# CONNECTORS.net
KiCad netlist of a schematic drawn in Altium Designer
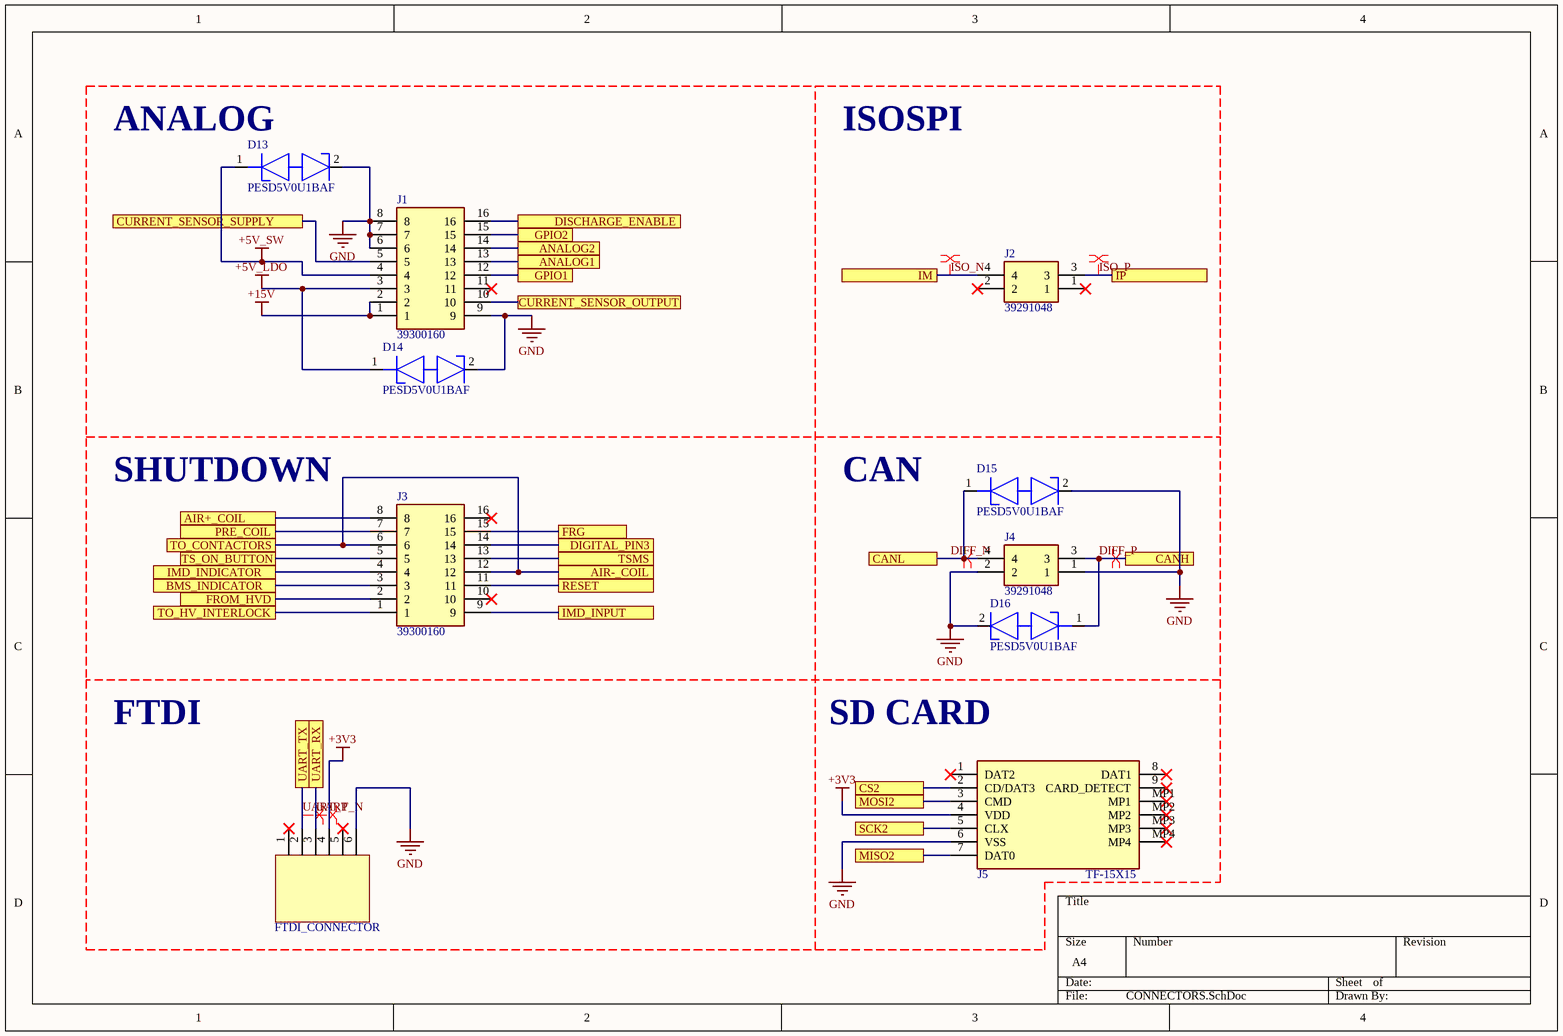
[diagram p0: CONNECTORS.SchDoc]

(export (version "E")
  (design (tool "Eeschema 10.0.6"))
  (components
    (comp (ref "*1")
      (value "FTDI_connector")
      (footprint "ARDUINO_MEGA_NO_SILK")
      (libsource (lib "Schlib1") (part "FTDI_connector"))
    )
    (comp (ref "D13")
      (value "PESD5V0U1BAF")
      (footprint "Regular_used_components_3D_Symbol:SOD2512X110N")
      (description "Diode ESD (Bi-directional)")
      (fields (field (name "MOUSER PART NUMBER") "771-PESD5V0U1BAF"))
      (libsource (lib "Regular_used_components_2D_Symbol") (part "PESD5V0U1BAF"))
    )
    (comp (ref "D14")
      (value "PESD5V0U1BAF")
      (footprint "Regular_used_components_3D_Symbol:SOD2512X110N")
      (description "Diode ESD (Bi-directional)")
      (fields (field (name "MOUSER PART NUMBER") "771-PESD5V0U1BAF"))
      (libsource (lib "Regular_used_components_2D_Symbol") (part "PESD5V0U1BAF"))
    )
    (comp (ref "D15")
      (value "PESD5V0U1BAF")
      (footprint "Regular_used_components_3D_Symbol:SOD2512X110N")
      (description "Diode ESD (Bi-directional)")
      (fields (field (name "MOUSER PART NUMBER") "771-PESD5V0U1BAF"))
      (libsource (lib "Regular_used_components_2D_Symbol") (part "PESD5V0U1BAF"))
    )
    (comp (ref "D16")
      (value "PESD5V0U1BAF")
      (footprint "Regular_used_components_3D_Symbol:SOD2512X110N")
      (description "Diode ESD (Bi-directional)")
      (fields (field (name "MOUSER PART NUMBER") "771-PESD5V0U1BAF"))
      (libsource (lib "Regular_used_components_2D_Symbol") (part "PESD5V0U1BAF"))
    )
    (comp (ref "J1")
      (value "39300160")
      (footprint "Regular_used_components_3D_Symbol:39300160")
      (description "Connector")
      (libsource (lib "*") (part "39300160"))
    )
    (comp (ref "J2")
      (value "39291048")
      (footprint "SamacSys:3929104Y")
      (description "Connector")
      (libsource (lib "*") (part "39291048"))
    )
    (comp (ref "J3")
      (value "39300160")
      (footprint "Regular_used_components_3D_Symbol:39300160")
      (description "Connector")
      (libsource (lib "*") (part "39300160"))
    )
    (comp (ref "J4")
      (value "39291048")
      (footprint "SamacSys:3929104Y")
      (description "Connector")
      (libsource (lib "*") (part "39291048"))
    )
    (comp (ref "J5")
      (value "TF-15X15")
      (footprint "Regular_used_components_3D_Symbol:TF15X15")
      (description "Connector")
      (libsource (lib "*") (part "TF-15X15"))
    )
  )
  (nets
    (net (code "1") (name "+3V3") (class "Default")
      (node (ref "*1") (pin "4") (pinfunction "4_4") (pintype "passive"))
      (node (ref "J5") (pin "4") (pinfunction "VDD_4") (pintype "passive"))
    )
    (net (code "2") (name "+5V_LDO") (class "Default")
      (node (ref "D14") (pin "1") (pinfunction "K1_1") (pintype "passive"))
      (node (ref "J1") (pin "3") (pinfunction "3_3") (pintype "passive"))
    )
    (net (code "3") (name "+5V_SW") (class "Default")
      (node (ref "D13") (pin "1") (pinfunction "K1_1") (pintype "passive"))
      (node (ref "J1") (pin "4") (pinfunction "4_4") (pintype "passive"))
    )
    (net (code "4") (name "+15V") (class "Default")
      (node (ref "J1") (pin "1") (pinfunction "1_1") (pintype "passive"))
      (node (ref "J1") (pin "2") (pinfunction "2_2") (pintype "passive"))
    )
    (net (code "5") (name "/AIR+_COIL") (class "Default")
      (node (ref "J3") (pin "8") (pinfunction "8_8") (pintype "passive"))
    )
    (net (code "6") (name "/AIR-_COIL") (class "Default")
      (node (ref "J3") (pin "12") (pinfunction "12_12") (pintype "passive"))
      (node (ref "J3") (pin "6") (pinfunction "6_6") (pintype "passive"))
    )
    (net (code "7") (name "/ANALOG1") (class "Default")
      (node (ref "J1") (pin "13") (pinfunction "13_13") (pintype "passive"))
    )
    (net (code "8") (name "/ANALOG2") (class "Default")
      (node (ref "J1") (pin "14") (pinfunction "14_14") (pintype "passive"))
    )
    (net (code "9") (name "/BMS_INDICATOR") (class "Default")
      (node (ref "J3") (pin "3") (pinfunction "3_3") (pintype "passive"))
    )
    (net (code "10") (name "/CS2") (class "Default")
      (node (ref "J5") (pin "2") (pinfunction "CD/DAT3_2") (pintype "passive"))
    )
    (net (code "11") (name "/CURRENT_SENSOR_OUTPUT") (class "Default")
      (node (ref "J1") (pin "10") (pinfunction "10_10") (pintype "passive"))
    )
    (net (code "12") (name "/CURRENT_SENSOR_SUPPLY") (class "Default")
      (node (ref "J1") (pin "5") (pinfunction "5_5") (pintype "passive"))
    )
    (net (code "13") (name "/DIFF_N") (class "Default")
      (node (ref "D15") (pin "1") (pinfunction "K1_1") (pintype "passive"))
      (node (ref "J4") (pin "4") (pinfunction "4_4") (pintype "passive"))
    )
    (net (code "14") (name "/DIFF_P") (class "Default")
      (node (ref "D16") (pin "1") (pinfunction "K1_1") (pintype "passive"))
      (node (ref "J4") (pin "3") (pinfunction "3_3") (pintype "passive"))
    )
    (net (code "15") (name "/DIGITAL_PIN3") (class "Default")
      (node (ref "J3") (pin "14") (pinfunction "14_14") (pintype "passive"))
    )
    (net (code "16") (name "/DISCHARGE_ENABLE") (class "Default")
      (node (ref "J1") (pin "16") (pinfunction "16_16") (pintype "passive"))
    )
    (net (code "17") (name "/FRG") (class "Default")
      (node (ref "J3") (pin "15") (pinfunction "15_15") (pintype "passive"))
    )
    (net (code "18") (name "/FROM_HVD") (class "Default")
      (node (ref "J3") (pin "2") (pinfunction "2_2") (pintype "passive"))
    )
    (net (code "19") (name "/GPIO1") (class "Default")
      (node (ref "J1") (pin "12") (pinfunction "12_12") (pintype "passive"))
    )
    (net (code "20") (name "/GPIO2") (class "Default")
      (node (ref "J1") (pin "15") (pinfunction "15_15") (pintype "passive"))
    )
    (net (code "21") (name "/IMD_INDICATOR") (class "Default")
      (node (ref "J3") (pin "4") (pinfunction "4_4") (pintype "passive"))
    )
    (net (code "22") (name "/IMD_INPUT") (class "Default")
      (node (ref "J3") (pin "9") (pinfunction "9_9") (pintype "passive"))
    )
    (net (code "23") (name "/ISO_N") (class "Default")
      (node (ref "J2") (pin "4") (pinfunction "4_4") (pintype "passive"))
    )
    (net (code "24") (name "/ISO_P") (class "Default")
      (node (ref "J2") (pin "3") (pinfunction "3_3") (pintype "passive"))
    )
    (net (code "25") (name "/MISO2") (class "Default")
      (node (ref "J5") (pin "7") (pinfunction "DAT0_7") (pintype "passive"))
    )
    (net (code "26") (name "/MOSI2") (class "Default")
      (node (ref "J5") (pin "3") (pinfunction "CMD_3") (pintype "passive"))
    )
    (net (code "27") (name "/PRE_COIL") (class "Default")
      (node (ref "J3") (pin "7") (pinfunction "7_7") (pintype "passive"))
    )
    (net (code "28") (name "/RESET") (class "Default")
      (node (ref "J3") (pin "11") (pinfunction "11_11") (pintype "passive"))
    )
    (net (code "29") (name "/SCK2") (class "Default")
      (node (ref "J5") (pin "5") (pinfunction "CLX_5") (pintype "passive"))
    )
    (net (code "30") (name "/TO_HV_INTERLOCK") (class "Default")
      (node (ref "J3") (pin "1") (pinfunction "1_1") (pintype "passive"))
    )
    (net (code "31") (name "/TSMS") (class "Default")
      (node (ref "J3") (pin "13") (pinfunction "13_13") (pintype "passive"))
    )
    (net (code "32") (name "/TS_ON_BUTTON") (class "Default")
      (node (ref "J3") (pin "5") (pinfunction "5_5") (pintype "passive"))
    )
    (net (code "33") (name "/UART_N") (class "Default")
      (node (ref "*1") (pin "3") (pinfunction "4_3") (pintype "passive"))
    )
    (net (code "34") (name "/UART_P") (class "Default")
      (node (ref "*1") (pin "2") (pinfunction "2_2") (pintype "passive"))
    )
    (net (code "35") (name "GND") (class "Default")
      (node (ref "*1") (pin "6") (pinfunction "6_6") (pintype "passive"))
      (node (ref "D13") (pin "2") (pinfunction "K2_2") (pintype "passive"))
      (node (ref "D14") (pin "2") (pinfunction "K2_2") (pintype "passive"))
      (node (ref "D15") (pin "2") (pinfunction "K2_2") (pintype "passive"))
      (node (ref "D16") (pin "2") (pinfunction "K2_2") (pintype "passive"))
      (node (ref "J1") (pin "6") (pinfunction "6_6") (pintype "passive"))
      (node (ref "J1") (pin "7") (pinfunction "7_7") (pintype "passive"))
      (node (ref "J1") (pin "8") (pinfunction "8_8") (pintype "passive"))
      (node (ref "J1") (pin "9") (pinfunction "9_9") (pintype "passive"))
      (node (ref "J4") (pin "1") (pinfunction "1_1") (pintype "passive"))
      (node (ref "J4") (pin "2") (pinfunction "2_2") (pintype "passive"))
      (node (ref "J5") (pin "6") (pinfunction "VSS_6") (pintype "passive"))
    )
    (net (code "36") (name "unconnected-(*1-2-Pad5)") (class "Default")
      (node (ref "*1") (pin "5") (pinfunction "2_5") (pintype "passive+no_connect"))
    )
    (net (code "37") (name "unconnected-(*1-Pad1)") (class "Default")
      (node (ref "*1") (pin "1") (pinfunction "1_1") (pintype "passive+no_connect"))
    )
    (net (code "38") (name "unconnected-(J1-Pad11)") (class "Default")
      (node (ref "J1") (pin "11") (pinfunction "11_11") (pintype "passive+no_connect"))
    )
    (net (code "39") (name "unconnected-(J2-Pad1)") (class "Default")
      (node (ref "J2") (pin "1") (pinfunction "1_1") (pintype "passive+no_connect"))
    )
    (net (code "40") (name "unconnected-(J2-Pad2)") (class "Default")
      (node (ref "J2") (pin "2") (pinfunction "2_2") (pintype "passive+no_connect"))
    )
    (net (code "41") (name "unconnected-(J3-Pad10)") (class "Default")
      (node (ref "J3") (pin "10") (pinfunction "10_10") (pintype "passive+no_connect"))
    )
    (net (code "42") (name "unconnected-(J3-Pad16)") (class "Default")
      (node (ref "J3") (pin "16") (pinfunction "16_16") (pintype "passive+no_connect"))
    )
    (net (code "43") (name "unconnected-(J5-CARD_DETECT-Pad9)") (class "Default")
      (node (ref "J5") (pin "9") (pinfunction "CARD_DETECT_9") (pintype "passive+no_connect"))
    )
    (net (code "44") (name "unconnected-(J5-DAT1-Pad8)") (class "Default")
      (node (ref "J5") (pin "8") (pinfunction "DAT1_8") (pintype "passive+no_connect"))
    )
    (net (code "45") (name "unconnected-(J5-DAT2-Pad1)") (class "Default")
      (node (ref "J5") (pin "1") (pinfunction "DAT2_1") (pintype "passive+no_connect"))
    )
    (net (code "46") (name "unconnected-(J5-PadMP1)") (class "Default")
      (node (ref "J5") (pin "MP1") (pinfunction "MP1_MP1") (pintype "passive+no_connect"))
    )
    (net (code "47") (name "unconnected-(J5-PadMP2)") (class "Default")
      (node (ref "J5") (pin "MP2") (pinfunction "MP2_MP2") (pintype "passive+no_connect"))
    )
    (net (code "48") (name "unconnected-(J5-PadMP3)") (class "Default")
      (node (ref "J5") (pin "MP3") (pinfunction "MP3_MP3") (pintype "passive+no_connect"))
    )
    (net (code "49") (name "unconnected-(J5-PadMP4)") (class "Default")
      (node (ref "J5") (pin "MP4") (pinfunction "MP4_MP4") (pintype "passive+no_connect"))
    )
  )
)
